# lab2_denikin_buck.net
KiCad netlist of a schematic drawn in Altium Designer
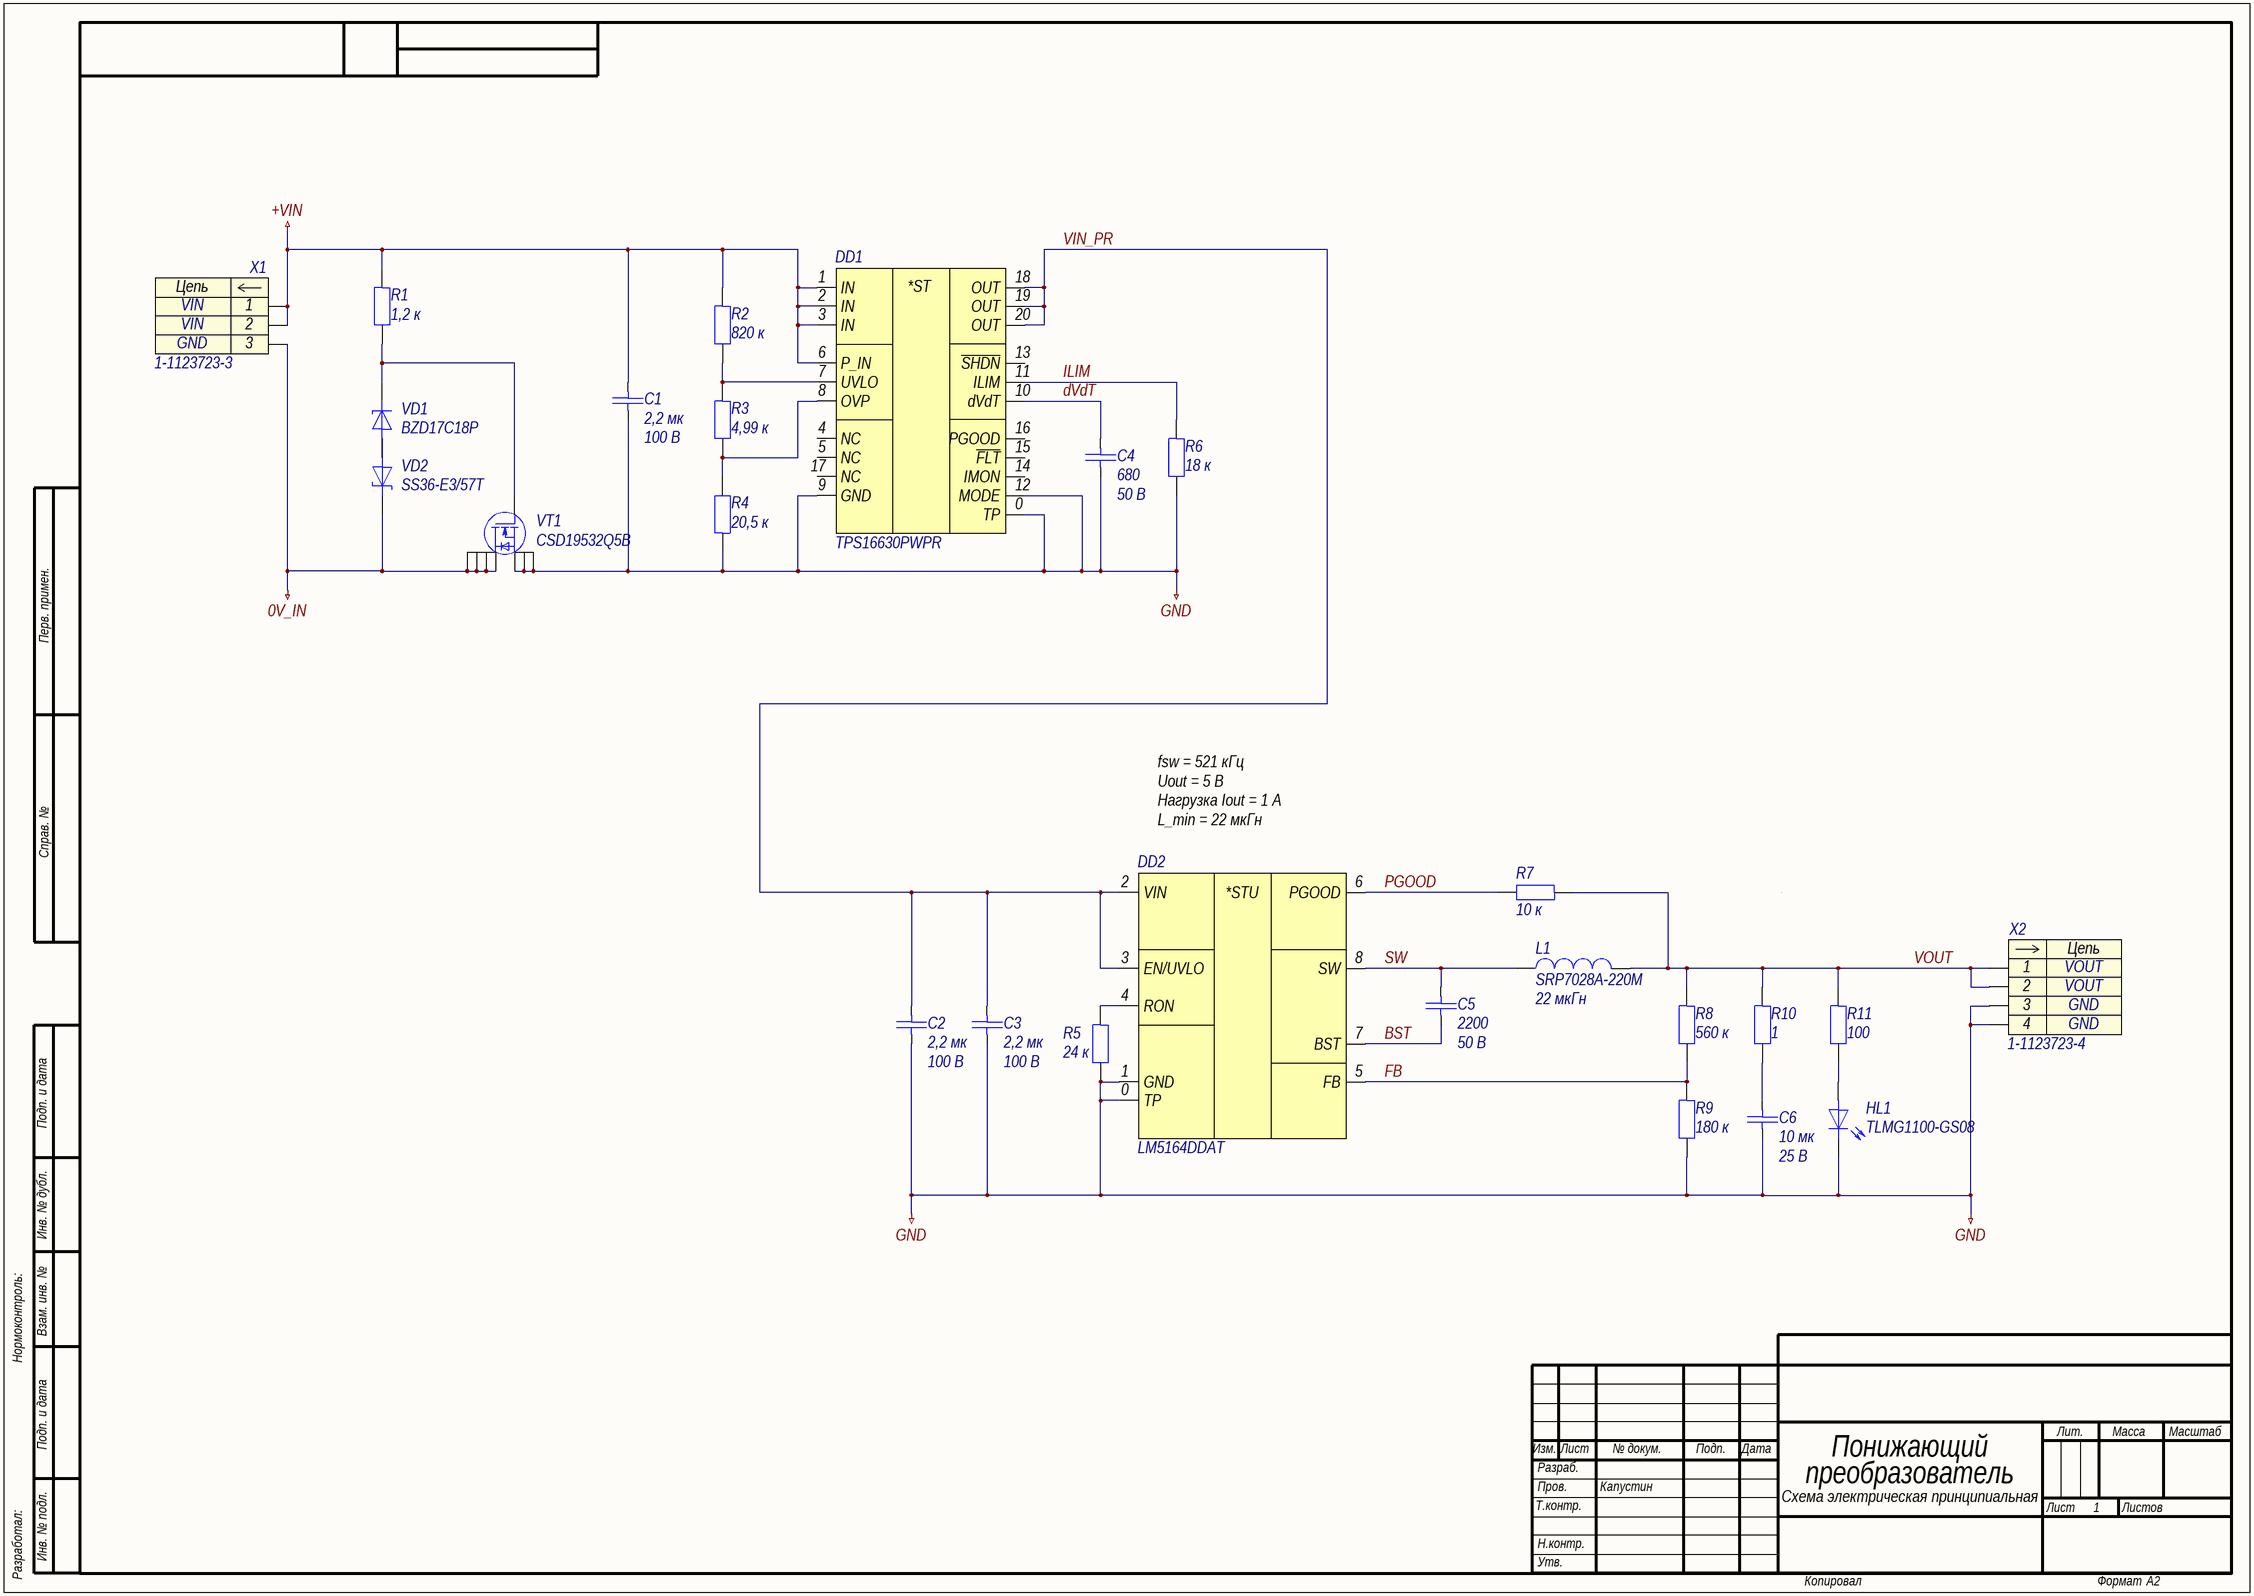
[diagram p0: lab2_denikin_buck.SchDoc]

(export (version "E")
  (design (tool "Eeschema 10.0.6"))
  (components
    (comp (ref "C1")
      (value "2,2 мк")
      (footprint "C1206")
      (description "=Описание")
      (fields (field (name "НАПРЯЖЕНИЕ") "100 В"))
      (libsource (lib "Database_Students") (part "C-NONPOLAR"))
    )
    (comp (ref "C2")
      (value "2,2 мк")
      (footprint "C1206")
      (description "=Описание")
      (fields (field (name "НАПРЯЖЕНИЕ") "100 В"))
      (libsource (lib "Database_Students") (part "C-NONPOLAR"))
    )
    (comp (ref "C3")
      (value "2,2 мк")
      (footprint "C1206")
      (description "=Описание")
      (fields (field (name "НАПРЯЖЕНИЕ") "100 В"))
      (libsource (lib "Database_Students") (part "C-NONPOLAR"))
    )
    (comp (ref "C4")
      (value "680")
      (footprint "C0603")
      (description "=Описание")
      (fields (field (name "НАПРЯЖЕНИЕ") "50 В"))
      (libsource (lib "Database_Students") (part "C-NONPOLAR"))
    )
    (comp (ref "C5")
      (value "2200")
      (footprint "C0603")
      (description "=Описание")
      (fields (field (name "НАПРЯЖЕНИЕ") "50 В"))
      (libsource (lib "Database_Students") (part "C-NONPOLAR"))
    )
    (comp (ref "C6")
      (value "10 мк")
      (footprint "C1206")
      (description "=Описание")
      (fields (field (name "НАПРЯЖЕНИЕ") "25 В"))
      (libsource (lib "Database_Students") (part "C-NONPOLAR"))
    )
    (comp (ref "DD1")
      (value "TPS16630PWPR")
      (footprint "HTSSOP-20")
      (description "=Описание")
      (libsource (lib "Database_Students") (part "TPS16630PWPR"))
    )
    (comp (ref "DD2")
      (value "LM5164DDAT")
      (footprint "HSOIC-8-P127-490X390X170-L84X41-T310X240")
      (description "=Описание")
      (libsource (lib "Database_Students") (part "LM5164QDDAT"))
    )
    (comp (ref "HL1")
      (value "TLMG1100-GS08")
      (footprint "HL0603")
      (description "=Описание")
      (libsource (lib "Database_Students") (part "HL-COMMON"))
    )
    (comp (ref "L1")
      (value "SRP7028A-220M")
      (footprint "SRP-2-670X660X280")
      (description "=Описание")
      (fields (field (name "ИНДУКТИВНОСТЬ") "22 мкГн"))
      (libsource (lib "Database_Students") (part "INDUCTOR-COMMON"))
    )
    (comp (ref "R1")
      (value "1,2 к")
      (footprint "R0603")
      (description "=Описание")
      (libsource (lib "Database_Students") (part "R-COMMON"))
    )
    (comp (ref "R2")
      (value "820 к")
      (footprint "R0603")
      (description "=Описание")
      (libsource (lib "Database_Students") (part "R-COMMON"))
    )
    (comp (ref "R3")
      (value "4,99 к")
      (footprint "R0603")
      (description "=Описание")
      (libsource (lib "Database_Students") (part "R-COMMON"))
    )
    (comp (ref "R4")
      (value "20,5 к")
      (footprint "R0603")
      (description "=Описание")
      (libsource (lib "Database_Students") (part "R-COMMON"))
    )
    (comp (ref "R5")
      (value "24 к")
      (footprint "R0603")
      (description "=Описание")
      (libsource (lib "Database_Students") (part "R-COMMON"))
    )
    (comp (ref "R6")
      (value "18 к")
      (footprint "R0603")
      (description "=Описание")
      (libsource (lib "Database_Students") (part "R-COMMON"))
    )
    (comp (ref "R7")
      (value "10 к")
      (footprint "R0603")
      (description "=Описание")
      (libsource (lib "Database_Students") (part "R-COMMON"))
    )
    (comp (ref "R8")
      (value "560 к")
      (footprint "R0603")
      (description "=Описание")
      (libsource (lib "Database_Students") (part "R-COMMON"))
    )
    (comp (ref "R9")
      (value "180 к")
      (footprint "R0603")
      (description "=Описание")
      (libsource (lib "Database_Students") (part "R-COMMON"))
    )
    (comp (ref "R10")
      (value "1")
      (footprint "R0603")
      (description "=Описание")
      (libsource (lib "Database_Students") (part "R-COMMON"))
    )
    (comp (ref "R11")
      (value "100")
      (footprint "R0603")
      (description "=Описание")
      (libsource (lib "Database_Students") (part "R-COMMON"))
    )
    (comp (ref "VD1")
      (value "BZD17C18P")
      (footprint "DO-219AB")
      (description "=Описание")
      (libsource (lib "Database_Students") (part "ZENER-DIODE"))
    )
    (comp (ref "VD2")
      (value "SS36-E3/57T")
      (footprint "DO-214AB")
      (description "=Описание")
      (libsource (lib "Database_Students") (part "DIODE-SCHOTTKY"))
    )
    (comp (ref "VT1")
      (value "CSD19532Q5B")
      (footprint "SON-8")
      (description "=Описание")
      (libsource (lib "Database_Students") (part "MOSFET-3S-4D"))
    )
    (comp (ref "X1")
      (value "1-1123723-3")
      (footprint "1-1123723-3")
      (description "=Описание")
      (libsource (lib "Database_Students") (part "HEADER-3-PLG"))
    )
    (comp (ref "X2")
      (value "1-1123723-4")
      (footprint "1-1123723-4")
      (description "=Описание")
      (libsource (lib "Database_Students") (part "HEADER-4-PLG"))
    )
  )
  (nets
    (net (code "1") (name "+VIN") (class "Default")
      (node (ref "C1") (pin "2") (pinfunction "2_2") (pintype "passive"))
      (node (ref "DD1") (pin "1") (pinfunction "IN_1") (pintype "passive"))
      (node (ref "DD1") (pin "2") (pinfunction "IN_2") (pintype "passive"))
      (node (ref "DD1") (pin "3") (pinfunction "IN_3") (pintype "passive"))
      (node (ref "DD1") (pin "6") (pinfunction "P_IN_6") (pintype "passive"))
      (node (ref "R1") (pin "1") (pinfunction "1_1") (pintype "passive"))
      (node (ref "R2") (pin "1") (pinfunction "1_1") (pintype "passive"))
      (node (ref "X1") (pin "1") (pinfunction "1_1") (pintype "passive"))
      (node (ref "X1") (pin "2") (pinfunction "2_2") (pintype "passive"))
    )
    (net (code "2") (name "/BST") (class "Default")
      (node (ref "C5") (pin "1") (pinfunction "1_1") (pintype "passive"))
      (node (ref "DD2") (pin "7") (pinfunction "BST_7") (pintype "passive"))
    )
    (net (code "3") (name "/FB") (class "Default")
      (node (ref "DD2") (pin "5") (pinfunction "FB_5") (pintype "passive"))
      (node (ref "R8") (pin "2") (pinfunction "2_2") (pintype "passive"))
      (node (ref "R9") (pin "1") (pinfunction "1_1") (pintype "passive"))
    )
    (net (code "4") (name "/ILIM") (class "Default")
      (node (ref "DD1") (pin "11") (pinfunction "ILIM_11") (pintype "passive"))
      (node (ref "R6") (pin "1") (pinfunction "1_1") (pintype "passive"))
    )
    (net (code "5") (name "/PGOOD") (class "Default")
      (node (ref "DD2") (pin "6") (pinfunction "PGOOD_6") (pintype "passive"))
      (node (ref "R7") (pin "2") (pinfunction "2_2") (pintype "passive"))
    )
    (net (code "6") (name "/SW") (class "Default")
      (node (ref "C5") (pin "2") (pinfunction "2_2") (pintype "passive"))
      (node (ref "DD2") (pin "8") (pinfunction "SW_8") (pintype "passive"))
      (node (ref "L1") (pin "1") (pinfunction "1_1") (pintype "passive"))
    )
    (net (code "7") (name "/VIN_PR") (class "Default")
      (node (ref "C2") (pin "2") (pinfunction "2_2") (pintype "passive"))
      (node (ref "C3") (pin "2") (pinfunction "2_2") (pintype "passive"))
      (node (ref "DD1") (pin "18") (pinfunction "OUT_18") (pintype "passive"))
      (node (ref "DD1") (pin "19") (pinfunction "OUT_19") (pintype "passive"))
      (node (ref "DD1") (pin "20") (pinfunction "OUT_20") (pintype "passive"))
      (node (ref "DD2") (pin "2") (pinfunction "VIN_2") (pintype "passive"))
      (node (ref "DD2") (pin "3") (pinfunction "EN/UVLO_3") (pintype "passive"))
    )
    (net (code "8") (name "/VOUT") (class "Default")
      (node (ref "L1") (pin "2") (pinfunction "2_2") (pintype "passive"))
      (node (ref "R10") (pin "1") (pinfunction "1_1") (pintype "passive"))
      (node (ref "R11") (pin "1") (pinfunction "1_1") (pintype "passive"))
      (node (ref "R7") (pin "1") (pinfunction "1_1") (pintype "passive"))
      (node (ref "R8") (pin "1") (pinfunction "1_1") (pintype "passive"))
      (node (ref "X2") (pin "1") (pinfunction "1_1") (pintype "passive"))
      (node (ref "X2") (pin "2") (pinfunction "2_2") (pintype "passive"))
    )
    (net (code "9") (name "/dVdT") (class "Default")
      (node (ref "C4") (pin "2") (pinfunction "2_2") (pintype "passive"))
      (node (ref "DD1") (pin "10") (pinfunction "dVdT_10") (pintype "passive"))
    )
    (net (code "10") (name "0V_IN") (class "Default")
      (node (ref "VD2") (pin "1") (pinfunction "1_1") (pintype "passive"))
      (node (ref "VT1") (pin "D") (pinfunction "D_D") (pintype "passive"))
      (node (ref "X1") (pin "3") (pinfunction "3_3") (pintype "passive"))
    )
    (net (code "11") (name "GND") (class "Default")
      (node (ref "C1") (pin "1") (pinfunction "1_1") (pintype "passive"))
      (node (ref "C2") (pin "1") (pinfunction "1_1") (pintype "passive"))
      (node (ref "C3") (pin "1") (pinfunction "1_1") (pintype "passive"))
      (node (ref "C4") (pin "1") (pinfunction "1_1") (pintype "passive"))
      (node (ref "C6") (pin "1") (pinfunction "1_1") (pintype "passive"))
      (node (ref "DD1") (pin "0") (pinfunction "TP_0") (pintype "passive"))
      (node (ref "DD1") (pin "12") (pinfunction "MODE_12") (pintype "passive"))
      (node (ref "DD1") (pin "9") (pinfunction "GND_9") (pintype "passive"))
      (node (ref "DD2") (pin "0") (pinfunction "TP_0") (pintype "passive"))
      (node (ref "DD2") (pin "1") (pinfunction "GND_1") (pintype "passive"))
      (node (ref "HL1") (pin "1") (pinfunction "1_1") (pintype "passive"))
      (node (ref "R4") (pin "1") (pinfunction "1_1") (pintype "passive"))
      (node (ref "R5") (pin "2") (pinfunction "2_2") (pintype "passive"))
      (node (ref "R6") (pin "2") (pinfunction "2_2") (pintype "passive"))
      (node (ref "R9") (pin "2") (pinfunction "2_2") (pintype "passive"))
      (node (ref "VT1") (pin "S") (pintype "passive"))
      (node (ref "X2") (pin "3") (pinfunction "3_3") (pintype "passive"))
      (node (ref "X2") (pin "4") (pinfunction "4_4") (pintype "passive"))
    )
    (net (code "12") (name "Net-(C6-Pad2)") (class "Default")
      (node (ref "C6") (pin "2") (pinfunction "2_2") (pintype "passive"))
      (node (ref "R10") (pin "2") (pinfunction "2_2") (pintype "passive"))
    )
    (net (code "13") (name "Net-(DD1-OVP)") (class "Default")
      (node (ref "DD1") (pin "8") (pinfunction "OVP_8") (pintype "passive"))
      (node (ref "R3") (pin "2") (pinfunction "2_2") (pintype "passive"))
      (node (ref "R4") (pin "2") (pinfunction "2_2") (pintype "passive"))
    )
    (net (code "14") (name "Net-(DD1-UVLO)") (class "Default")
      (node (ref "DD1") (pin "7") (pinfunction "UVLO_7") (pintype "passive"))
      (node (ref "R2") (pin "2") (pinfunction "2_2") (pintype "passive"))
      (node (ref "R3") (pin "1") (pinfunction "1_1") (pintype "passive"))
    )
    (net (code "15") (name "Net-(DD2-RON)") (class "Default")
      (node (ref "DD2") (pin "4") (pinfunction "RON_4") (pintype "passive"))
      (node (ref "R5") (pin "1") (pinfunction "1_1") (pintype "passive"))
    )
    (net (code "16") (name "Net-(HL1-Pad2)") (class "Default")
      (node (ref "HL1") (pin "2") (pinfunction "2_2") (pintype "passive"))
      (node (ref "R11") (pin "2") (pinfunction "2_2") (pintype "passive"))
    )
    (net (code "17") (name "Net-(R1-Pad2)") (class "Default")
      (node (ref "R1") (pin "2") (pinfunction "2_2") (pintype "passive"))
      (node (ref "VD1") (pin "1") (pinfunction "1_1") (pintype "passive"))
      (node (ref "VT1") (pin "G") (pinfunction "G_G") (pintype "passive"))
    )
    (net (code "18") (name "Net-(VD1-Pad2)") (class "Default")
      (node (ref "VD1") (pin "2") (pinfunction "2_2") (pintype "passive"))
      (node (ref "VD2") (pin "2") (pinfunction "2_2") (pintype "passive"))
    )
    (net (code "19") (name "unconnected-(DD1-IMON-Pad14)") (class "Default")
      (node (ref "DD1") (pin "14") (pinfunction "IMON_14") (pintype "passive"))
    )
    (net (code "20") (name "unconnected-(DD1-NC-Pad4)") (class "Default")
      (node (ref "DD1") (pin "4") (pinfunction "NC_4") (pintype "passive"))
    )
    (net (code "21") (name "unconnected-(DD1-NC-Pad5)") (class "Default")
      (node (ref "DD1") (pin "5") (pinfunction "NC_5") (pintype "passive"))
    )
    (net (code "22") (name "unconnected-(DD1-NC-Pad17)") (class "Default")
      (node (ref "DD1") (pin "17") (pinfunction "NC_17") (pintype "passive"))
    )
    (net (code "23") (name "unconnected-(DD1-PGOOD-Pad16)") (class "Default")
      (node (ref "DD1") (pin "16") (pinfunction "PGOOD_16") (pintype "passive"))
    )
    (net (code "24") (name "unconnected-(DD1-~{FLT}-Pad15)") (class "Default")
      (node (ref "DD1") (pin "15") (pinfunction "~{FLT}_15") (pintype "passive"))
    )
    (net (code "25") (name "unconnected-(DD1-~{SHDN}-Pad13)") (class "Default")
      (node (ref "DD1") (pin "13") (pinfunction "~{SHDN}_13") (pintype "passive"))
    )
  )
)
